# BMA180.net
KiCad netlist of a schematic drawn in Altium Designer
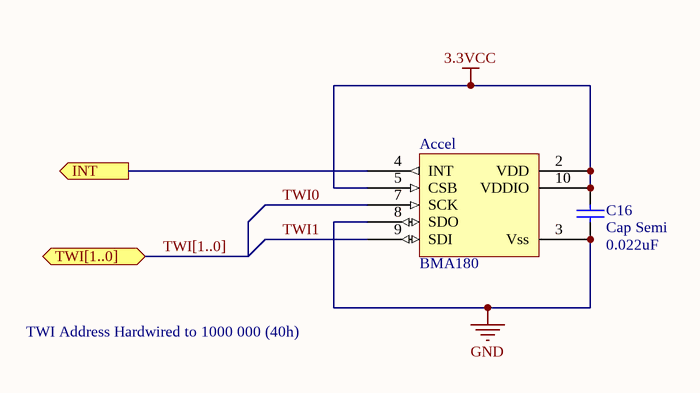
[diagram p0: BMA180.SchDoc]

(export (version "E")
  (design (tool "Eeschema 10.0.6"))
  (components
    (comp (ref "Accel")
      (value "BMA180")
      (footprint "BMA180 - ECESHOP")
      (libsource (lib "BMA180") (part "BMA180"))
    )
    (comp (ref "C16")
      (value "Cap Semi")
      (footprint "CAPC2012N")
      (description "Capacitor (Semiconductor SIM Model)")
      (fields (field (name "ALTIUM_VALUE") "0.022uF") (field (name "PUBLISHER") "Altium Limited"))
      (libsource (lib "Miscellaneous Devices") (part "Cap Semi"))
    )
  )
  (nets
    (net (code "1") (name "/INT") (class "Default")
      (node (ref "Accel") (pin "4") (pinfunction "INT_4") (pintype "output"))
    )
    (net (code "2") (name "/TWI0") (class "Default")
      (node (ref "Accel") (pin "7") (pinfunction "SCK_7") (pintype "input"))
    )
    (net (code "3") (name "/TWI1") (class "Default")
      (node (ref "Accel") (pin "9") (pinfunction "SDI_9") (pintype "bidirectional"))
    )
    (net (code "5") (name "3.3VCC") (class "Default")
      (node (ref "Accel") (pin "10") (pinfunction "VDDIO_10") (pintype "passive"))
      (node (ref "Accel") (pin "2") (pinfunction "VDD_2") (pintype "power_in"))
      (node (ref "Accel") (pin "5") (pinfunction "CSB_5") (pintype "input"))
      (node (ref "C16") (pin "2") (pinfunction "2_2") (pintype "passive"))
    )
    (net (code "6") (name "GND") (class "Default")
      (node (ref "Accel") (pin "3") (pinfunction "Vss_3") (pintype "passive"))
      (node (ref "Accel") (pin "8") (pinfunction "SDO_8") (pintype "bidirectional"))
      (node (ref "C16") (pin "1") (pinfunction "1_1") (pintype "passive"))
    )
  )
)
